# COMM.net
KiCad netlist of a schematic drawn in Altium Designer
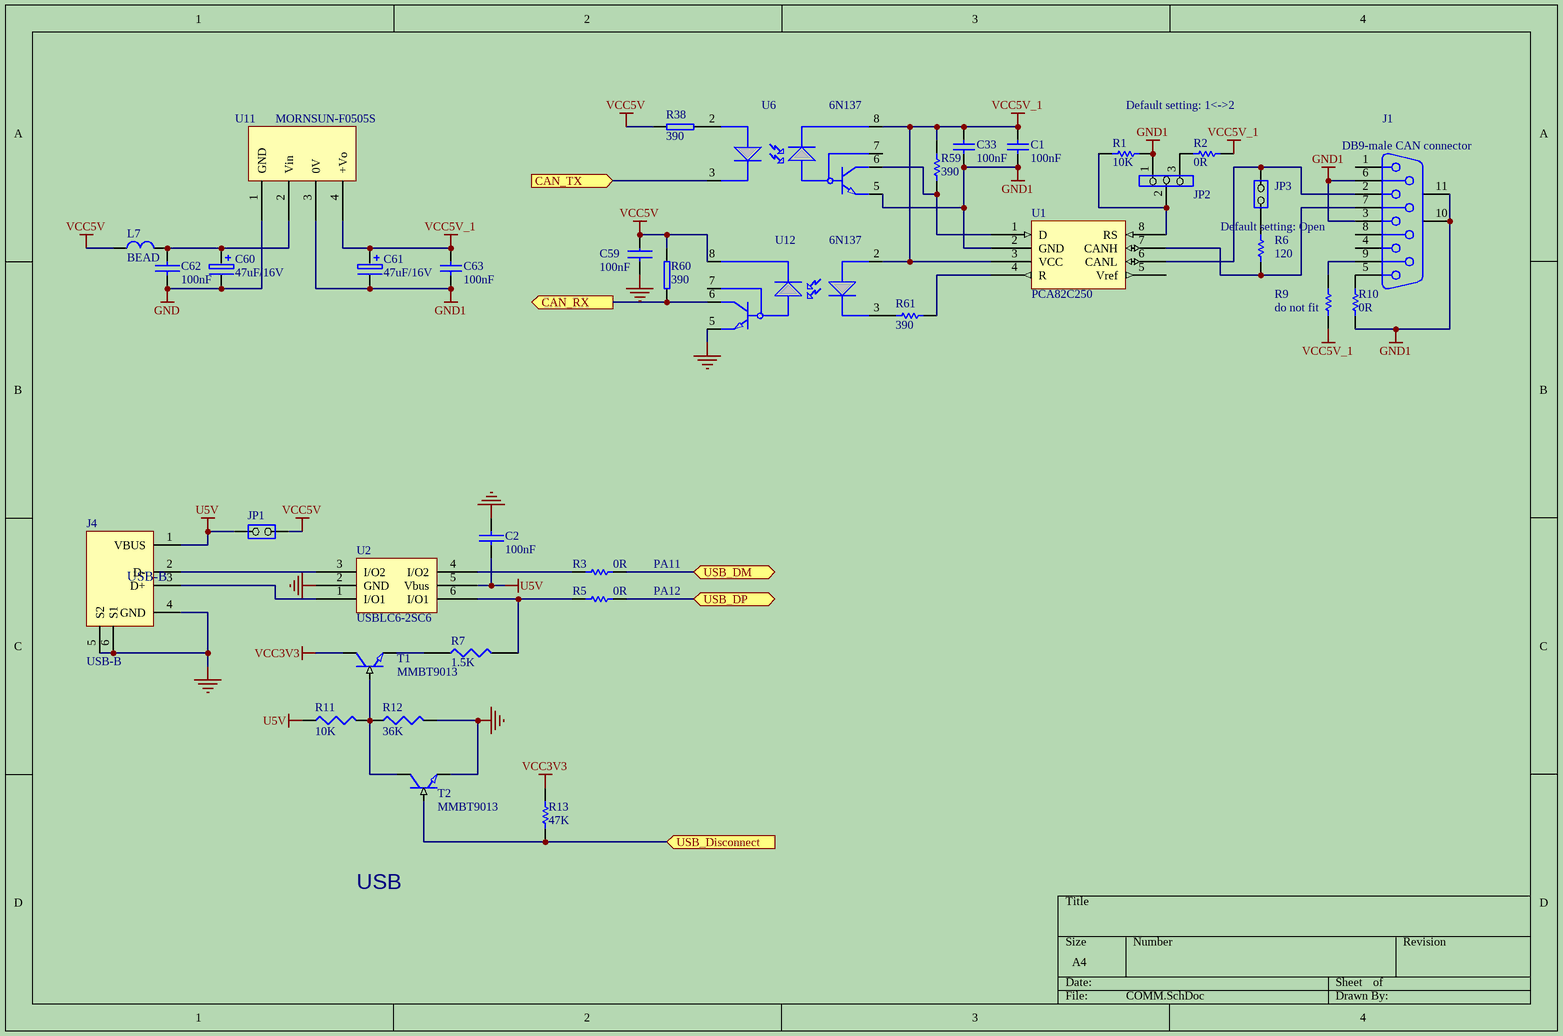
[diagram p0: COMM.SchDoc]

(export (version "E")
  (design (tool "Eeschema 10.0.6"))
  (components
    (comp (ref "C1")
      (value "100nF")
      (footprint "C0805")
      (description "Capacitor")
      (fields (field (name "PUBLISHER") "Altium Limited"))
      (libsource (lib "Miscellaneous Devices") (part "CAP"))
    )
    (comp (ref "C2")
      (value "100nF")
      (footprint "C0805")
      (description "Capacitor")
      (libsource (lib "*") (part "CAP"))
    )
    (comp (ref "C33")
      (value "100nF")
      (footprint "C0805")
      (description "Capacitor")
      (fields (field (name "PUBLISHER") "Altium Limited"))
      (libsource (lib "Miscellaneous Devices") (part "CAP"))
    )
    (comp (ref "C59") (value "100nF") (footprint "C0805") (libsource (lib "*") (part "CAP NP")))
    (comp (ref "C60")
      (value "47uF/16V")
      (footprint "CD1/2")
      (description "Electrolytic Capacitor")
      (libsource (lib "*") (part "CD1"))
    )
    (comp (ref "C61")
      (value "47uF/16V")
      (footprint "CD1/2")
      (description "Electrolytic Capacitor")
      (libsource (lib "*") (part "CD1"))
    )
    (comp (ref "C62")
      (value "100nF")
      (footprint "C0805")
      (description "Capacitor")
      (libsource (lib "*") (part "CC"))
    )
    (comp (ref "C63")
      (value "100nF")
      (footprint "C0805")
      (description "Capacitor")
      (fields (field (name "PUBLISHER") "Altium Limited"))
      (libsource (lib "Miscellaneous Devices") (part "CAP"))
    )
    (comp (ref "J1")
      (value "DB9-male CAN connector")
      (footprint "DSUB1.385-2H9")
      (description "Receptacle Assembly, 9 Position, Right Angle")
      (fields (field (name "PUBLISHER") "Altium Limited"))
      (libsource (lib "Miscellaneous Connectors") (part "D Connector 9"))
    )
    (comp (ref "J4") (value "USB-B") (footprint "USB-B") (libsource (lib "Devices") (part "USB-B")))
    (comp (ref "JP1") (value "~") (footprint "SIP2") (libsource (lib "*") (part "JP2")))
    (comp (ref "JP2") (value "~") (footprint "SIP3") (libsource (lib "STR910_SCHLIB") (part "Jumper3")))
    (comp (ref "JP3") (value "~") (footprint "SIP2") (libsource (lib "*") (part "JP2")))
    (comp (ref "L7") (value "BEAD") (footprint "L0805") (libsource (lib "*") (part "L1")))
    (comp (ref "R1")
      (value "10K")
      (footprint "R0805")
      (description "Resistor")
      (fields (field (name "PUBLISHER") "Altium Limited"))
      (libsource (lib "Miscellaneous Devices") (part "res1"))
    )
    (comp (ref "R2")
      (value "0R")
      (footprint "R0805")
      (description "Resistor")
      (fields (field (name "PUBLISHER") "Altium Limited"))
      (libsource (lib "Miscellaneous Devices") (part "res1"))
    )
    (comp (ref "R3")
      (value "0R")
      (footprint "R0805")
      (description "Resistor")
      (fields (field (name "PUBLISHER") "Altium Limited"))
      (libsource (lib "") (part "Res1_1"))
    )
    (comp (ref "R5")
      (value "0R")
      (footprint "R0805")
      (description "Resistor")
      (fields (field (name "PUBLISHER") "Altium Limited"))
      (libsource (lib "") (part "Res1_1"))
    )
    (comp (ref "R6")
      (value "120")
      (footprint "R0805")
      (description "Resistor")
      (fields (field (name "PUBLISHER") "Altium Limited"))
      (libsource (lib "Miscellaneous Devices") (part "res1"))
    )
    (comp (ref "R7") (value "1.5K") (footprint "R0805") (libsource (lib "*") (part "RES1")))
    (comp (ref "R9")
      (value "do not fit")
      (footprint "R0805")
      (description "Resistor")
      (fields (field (name "PUBLISHER") "Altium Limited"))
      (libsource (lib "Miscellaneous Devices") (part "res1"))
    )
    (comp (ref "R10")
      (value "0R")
      (footprint "R0805")
      (description "Resistor")
      (fields (field (name "PUBLISHER") "Altium Limited"))
      (libsource (lib "Miscellaneous Devices") (part "res1"))
    )
    (comp (ref "R11") (value "10K") (footprint "R0805") (libsource (lib "*") (part "R")))
    (comp (ref "R12") (value "36K") (footprint "R0805") (libsource (lib "*") (part "R")))
    (comp (ref "R13")
      (value "47K")
      (footprint "R0805")
      (description "Resistor")
      (fields (field (name "PUBLISHER") "Altium Limited"))
      (libsource (lib "") (part "Res1_1"))
    )
    (comp (ref "R38")
      (value "390")
      (footprint "R0805")
      (description "Resistor")
      (libsource (lib "") (part "R_1"))
    )
    (comp (ref "R59")
      (value "390")
      (footprint "R0805")
      (description "Resistor")
      (fields (field (name "PUBLISHER") "Altium Limited"))
      (libsource (lib "Miscellaneous Devices") (part "Res1"))
    )
    (comp (ref "R60")
      (value "390")
      (footprint "R0805")
      (description "Resistor")
      (libsource (lib "") (part "R_1"))
    )
    (comp (ref "R61")
      (value "390")
      (footprint "R0805")
      (description "Resistor")
      (fields (field (name "PUBLISHER") "Altium Limited"))
      (libsource (lib "Miscellaneous Devices") (part "Res1"))
    )
    (comp (ref "T1") (value "MMBT9013") (footprint "SOT-23") (libsource (lib "Devices") (part "NPN_SOT23")))
    (comp (ref "T2") (value "MMBT9013") (footprint "SOT-23") (libsource (lib "Devices") (part "NPN_SOT23")))
    (comp (ref "U1")
      (value "PCA82C250")
      (footprint "SO8")
      (libsource (lib "STR910_SCHLIB") (part "SN65HVD230D"))
    )
    (comp (ref "U2")
      (value "USBLC6-2SC6")
      (footprint "SOT-23/6")
      (libsource (lib "STR910_SCHLIB") (part "USBLC6-2"))
    )
    (comp (ref "U6") (value "6N137") (footprint "DIP8") (libsource (lib "*") (part "6N136")))
    (comp (ref "U11")
      (value "MORNSUN-F0505S")
      (footprint "MORNSUN-BM")
      (description "MORNSUN Fixed input,Isolated,Unregulated Series DC/DC")
      (libsource (lib "*") (part "MORNSUN-BM"))
    )
    (comp (ref "U12") (value "6N137") (footprint "DIP8") (libsource (lib "*") (part "6N136")))
  )
  (nets
    (net (code "1") (name "/CAN_RX") (class "Default")
      (node (ref "R60") (pin "2") (pinfunction "2_2") (pintype "passive"))
      (node (ref "U12") (pin "6") (pinfunction "6_6") (pintype "passive"))
    )
    (net (code "2") (name "/CAN_TX") (class "Default")
      (node (ref "U6") (pin "3") (pinfunction "3_3") (pintype "passive"))
    )
    (net (code "3") (name "/USB_DM") (class "Default")
      (node (ref "R3") (pin "1") (pinfunction "1_1") (pintype "passive"))
    )
    (net (code "4") (name "/USB_DP") (class "Default")
      (node (ref "R5") (pin "1") (pinfunction "1_1") (pintype "passive"))
    )
    (net (code "5") (name "/USB_Disconnect") (class "Default")
      (node (ref "R13") (pin "1") (pinfunction "1_1") (pintype "passive"))
      (node (ref "T2") (pin "1") (pinfunction "B_1") (pintype "input"))
    )
    (net (code "6") (name "GND") (class "Default")
      (node (ref "C2") (pin "1") (pinfunction "1_1") (pintype "passive"))
      (node (ref "C59") (pin "2") (pinfunction "2_2") (pintype "passive"))
      (node (ref "C60") (pin "2") (pinfunction "2_2") (pintype "passive"))
      (node (ref "C62") (pin "2") (pinfunction "2_2") (pintype "passive"))
      (node (ref "J4") (pin "4") (pinfunction "GND_4") (pintype "passive"))
      (node (ref "J4") (pin "5") (pinfunction "S2_5") (pintype "passive"))
      (node (ref "J4") (pin "6") (pinfunction "S1_6") (pintype "passive"))
      (node (ref "R12") (pin "2") (pinfunction "2_2") (pintype "passive"))
      (node (ref "T2") (pin "2") (pinfunction "E_2") (pintype "open_emitter"))
      (node (ref "U11") (pin "1") (pinfunction "GND_1") (pintype "passive"))
      (node (ref "U12") (pin "5") (pinfunction "5_5") (pintype "passive"))
      (node (ref "U2") (pin "2") (pinfunction "GND_2") (pintype "passive"))
    )
    (net (code "7") (name "GND1") (class "Default")
      (node (ref "C1") (pin "2") (pinfunction "2_2") (pintype "passive"))
      (node (ref "C33") (pin "2") (pinfunction "2_2") (pintype "passive"))
      (node (ref "C61") (pin "2") (pinfunction "2_2") (pintype "passive"))
      (node (ref "C63") (pin "2") (pinfunction "2_2") (pintype "passive"))
      (node (ref "J1") (pin "10") (pinfunction "MH1_10") (pintype "passive"))
      (node (ref "J1") (pin "11") (pinfunction "MH2_11") (pintype "passive"))
      (node (ref "J1") (pin "3") (pinfunction "3_3") (pintype "passive"))
      (node (ref "J1") (pin "6") (pinfunction "6_6") (pintype "passive"))
      (node (ref "JP2") (pin "1") (pintype "passive"))
      (node (ref "R1") (pin "2") (pinfunction "2_2") (pintype "passive"))
      (node (ref "R10") (pin "1") (pinfunction "1_1") (pintype "passive"))
      (node (ref "U1") (pin "2") (pinfunction "GND_2") (pintype "power_in"))
      (node (ref "U11") (pin "3") (pinfunction "0V_3") (pintype "passive"))
      (node (ref "U6") (pin "5") (pinfunction "5_5") (pintype "passive"))
    )
    (net (code "8") (name "Net-(J1-Pad5)") (class "Default")
      (node (ref "J1") (pin "5") (pinfunction "5_5") (pintype "passive"))
      (node (ref "R10") (pin "2") (pinfunction "2_2") (pintype "passive"))
    )
    (net (code "9") (name "Net-(J1-Pad9)") (class "Default")
      (node (ref "J1") (pin "9") (pinfunction "9_9") (pintype "passive"))
      (node (ref "R9") (pin "2") (pinfunction "2_2") (pintype "passive"))
    )
    (net (code "10") (name "Net-(J4-D+)") (class "Default")
      (node (ref "J4") (pin "3") (pinfunction "D+_3") (pintype "passive"))
      (node (ref "U2") (pin "1") (pinfunction "I/O1_1") (pintype "passive"))
    )
    (net (code "11") (name "Net-(J4-D-)") (class "Default")
      (node (ref "J4") (pin "2") (pinfunction "D-_2") (pintype "passive"))
      (node (ref "U2") (pin "3") (pinfunction "I/O2_3") (pintype "passive"))
    )
    (net (code "12") (name "Net-(JP2-Pad3)") (class "Default")
      (node (ref "JP2") (pin "3") (pintype "passive"))
      (node (ref "R2") (pin "1") (pinfunction "1_1") (pintype "passive"))
    )
    (net (code "13") (name "Net-(JP3-COMMON)") (class "Default")
      (node (ref "JP3") (pin "1") (pinfunction "COMMON_1") (pintype "passive"))
      (node (ref "R6") (pin "2") (pinfunction "2_2") (pintype "passive"))
    )
    (net (code "14") (name "Net-(JP3-NO)") (class "Default")
      (node (ref "J1") (pin "2") (pinfunction "2_2") (pintype "passive"))
      (node (ref "JP3") (pin "2") (pinfunction "NO_2") (pintype "passive"))
      (node (ref "U1") (pin "6") (pinfunction "CANL_6") (pintype "bidirectional"))
    )
    (net (code "15") (name "Net-(R3-Pad2)") (class "Default")
      (node (ref "R3") (pin "2") (pinfunction "2_2") (pintype "passive"))
      (node (ref "U2") (pin "4") (pinfunction "I/O2_4") (pintype "passive"))
    )
    (net (code "16") (name "Net-(R5-Pad2)") (class "Default")
      (node (ref "R5") (pin "2") (pinfunction "2_2") (pintype "passive"))
      (node (ref "R7") (pin "2") (pinfunction "2_2") (pintype "passive"))
      (node (ref "U2") (pin "6") (pinfunction "I/O1_6") (pintype "passive"))
    )
    (net (code "17") (name "Net-(R38-Pad1)") (class "Default")
      (node (ref "R38") (pin "1") (pinfunction "1_1") (pintype "passive"))
      (node (ref "U6") (pin "2") (pinfunction "2_2") (pintype "passive"))
    )
    (net (code "18") (name "Net-(R61-Pad2)") (class "Default")
      (node (ref "R61") (pin "2") (pinfunction "2_2") (pintype "passive"))
      (node (ref "U12") (pin "3") (pinfunction "3_3") (pintype "passive"))
    )
    (net (code "19") (name "Net-(T1-B)") (class "Default")
      (node (ref "R11") (pin "2") (pinfunction "2_2") (pintype "passive"))
      (node (ref "R12") (pin "1") (pinfunction "1_1") (pintype "passive"))
      (node (ref "T1") (pin "1") (pinfunction "B_1") (pintype "input"))
      (node (ref "T2") (pin "3") (pinfunction "C_3") (pintype "open_collector"))
    )
    (net (code "20") (name "Net-(T1-E)") (class "Default")
      (node (ref "R7") (pin "1") (pinfunction "1_1") (pintype "passive"))
      (node (ref "T1") (pin "2") (pinfunction "E_2") (pintype "open_emitter"))
    )
    (net (code "21") (name "Net-(U1-CANH)") (class "Default")
      (node (ref "J1") (pin "7") (pinfunction "7_7") (pintype "passive"))
      (node (ref "R6") (pin "1") (pinfunction "1_1") (pintype "passive"))
      (node (ref "U1") (pin "7") (pinfunction "CANH_7") (pintype "bidirectional"))
    )
    (net (code "22") (name "Net-(U1-D)") (class "Default")
      (node (ref "R59") (pin "1") (pinfunction "1_1") (pintype "passive"))
      (node (ref "U1") (pin "1") (pinfunction "D_1") (pintype "input"))
      (node (ref "U6") (pin "6") (pinfunction "6_6") (pintype "passive"))
    )
    (net (code "23") (name "Net-(U1-R)") (class "Default")
      (node (ref "R61") (pin "1") (pinfunction "1_1") (pintype "passive"))
      (node (ref "U1") (pin "4") (pinfunction "R_4") (pintype "output"))
    )
    (net (code "24") (name "Net-(U1-RS)") (class "Default")
      (node (ref "JP2") (pin "2") (pintype "passive"))
      (node (ref "R1") (pin "1") (pinfunction "1_1") (pintype "passive"))
      (node (ref "U1") (pin "8") (pinfunction "RS_8") (pintype "input"))
    )
    (net (code "25") (name "Net-(U11-Vin)") (class "Default")
      (node (ref "C60") (pin "1") (pinfunction "1_1") (pintype "passive"))
      (node (ref "C62") (pin "1") (pinfunction "1_1") (pintype "passive"))
      (node (ref "L7") (pin "2") (pinfunction "2_2") (pintype "passive"))
      (node (ref "U11") (pin "2") (pinfunction "Vin_2") (pintype "passive"))
    )
    (net (code "26") (name "U5V") (class "Default")
      (node (ref "C2") (pin "2") (pinfunction "2_2") (pintype "passive"))
      (node (ref "J4") (pin "1") (pinfunction "VBUS_1") (pintype "passive"))
      (node (ref "JP1") (pin "2") (pinfunction "NO_2") (pintype "passive"))
      (node (ref "R11") (pin "1") (pinfunction "1_1") (pintype "passive"))
      (node (ref "U2") (pin "5") (pinfunction "Vbus_5") (pintype "passive"))
    )
    (net (code "27") (name "VCC3V3") (class "Default")
      (node (ref "R13") (pin "2") (pinfunction "2_2") (pintype "passive"))
      (node (ref "T1") (pin "3") (pinfunction "C_3") (pintype "open_collector"))
    )
    (net (code "28") (name "VCC5V") (class "Default")
      (node (ref "C59") (pin "1") (pinfunction "1_1") (pintype "passive"))
      (node (ref "JP1") (pin "1") (pinfunction "COMMON_1") (pintype "passive"))
      (node (ref "L7") (pin "1") (pinfunction "1_1") (pintype "passive"))
      (node (ref "R38") (pin "2") (pinfunction "2_2") (pintype "passive"))
      (node (ref "R60") (pin "1") (pinfunction "1_1") (pintype "passive"))
      (node (ref "U12") (pin "8") (pinfunction "8_8") (pintype "passive"))
    )
    (net (code "29") (name "VCC5V_1") (class "Default")
      (node (ref "C1") (pin "1") (pinfunction "1_1") (pintype "passive"))
      (node (ref "C33") (pin "1") (pinfunction "1_1") (pintype "passive"))
      (node (ref "C61") (pin "1") (pinfunction "1_1") (pintype "passive"))
      (node (ref "C63") (pin "1") (pinfunction "1_1") (pintype "passive"))
      (node (ref "R2") (pin "2") (pinfunction "2_2") (pintype "passive"))
      (node (ref "R59") (pin "2") (pinfunction "2_2") (pintype "passive"))
      (node (ref "R9") (pin "1") (pinfunction "1_1") (pintype "passive"))
      (node (ref "U1") (pin "3") (pinfunction "VCC_3") (pintype "power_in"))
      (node (ref "U11") (pin "4") (pinfunction "+Vo_4") (pintype "passive"))
      (node (ref "U12") (pin "2") (pinfunction "2_2") (pintype "passive"))
      (node (ref "U6") (pin "8") (pinfunction "8_8") (pintype "passive"))
    )
    (net (code "30") (name "unconnected-(J1-Pad1)") (class "Default")
      (node (ref "J1") (pin "1") (pinfunction "1_1") (pintype "passive"))
    )
    (net (code "31") (name "unconnected-(J1-Pad4)") (class "Default")
      (node (ref "J1") (pin "4") (pinfunction "4_4") (pintype "passive"))
    )
    (net (code "32") (name "unconnected-(J1-Pad8)") (class "Default")
      (node (ref "J1") (pin "8") (pinfunction "8_8") (pintype "passive"))
    )
    (net (code "33") (name "unconnected-(U1-Vref-Pad5)") (class "Default")
      (node (ref "U1") (pin "5") (pinfunction "Vref_5") (pintype "output"))
    )
    (net (code "34") (name "unconnected-(U6-Pad7)") (class "Default")
      (node (ref "U6") (pin "7") (pinfunction "7_7") (pintype "passive"))
    )
    (net (code "35") (name "unconnected-(U12-Pad7)") (class "Default")
      (node (ref "U12") (pin "7") (pinfunction "7_7") (pintype "passive"))
    )
  )
)
